# Sensor.net
KiCad netlist of a schematic drawn in Altium Designer
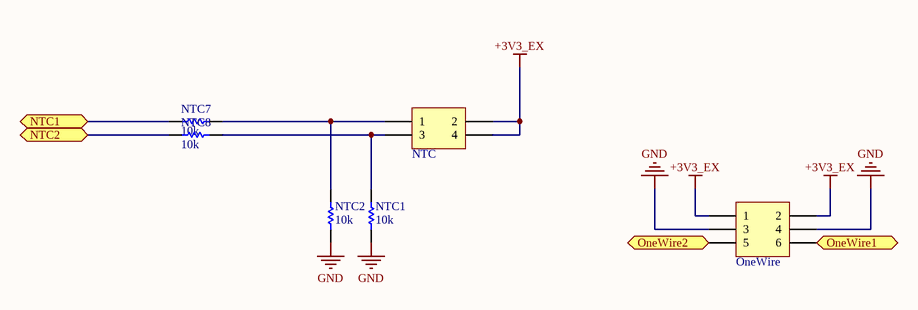
[diagram p0: Sensor.SchDoc]

(export (version "E")
  (design (tool "Eeschema 10.0.6"))
  (components
    (comp (ref "NTC")
      (value "Header 2X2")
      (footprint "heromap:HDR2X2")
      (description "Header, 2-Pin, Dual row")
      (fields (field (name "PUBLISHER") "Altium Limited"))
      (libsource (lib "heromap") (part "Header 2X2"))
    )
    (comp (ref "NTC1")
      (value "10k")
      (footprint "RESC1608N_ZERO")
      (fields (field (name "Comment") "Res"))
      (libsource (lib "Tuan") (part "Res"))
    )
    (comp (ref "NTC2")
      (value "10k")
      (footprint "RESC1608N_ZERO")
      (fields (field (name "Comment") "Res"))
      (libsource (lib "Tuan") (part "Res"))
    )
    (comp (ref "NTC7")
      (value "10k")
      (footprint "RESC1608N_ZERO")
      (fields (field (name "Comment") "Res"))
      (libsource (lib "Tuan") (part "Res"))
    )
    (comp (ref "NTC8")
      (value "10k")
      (footprint "RESC1608N_ZERO")
      (fields (field (name "Comment") "Res"))
      (libsource (lib "Tuan") (part "Res"))
    )
    (comp (ref "OneWire")
      (value "Header 3X2")
      (footprint "heromap:HDR2X3")
      (description "Header, 3-Pin, Dual row")
      (fields (field (name "PUBLISHER") "Altium Limited"))
      (libsource (lib "heromap") (part "Header 3X2"))
    )
  )
  (nets
    (net (code "1") (name "+3V3_EX") (class "Default")
      (node (ref "NTC") (pin "2") (pinfunction "2_2") (pintype "passive"))
      (node (ref "NTC") (pin "4") (pinfunction "4_4") (pintype "passive"))
      (node (ref "OneWire") (pin "1") (pinfunction "1_1") (pintype "passive"))
      (node (ref "OneWire") (pin "2") (pinfunction "2_2") (pintype "passive"))
    )
    (net (code "2") (name "/NTC1") (class "Default")
      (node (ref "NTC7") (pin "2") (pinfunction "2_2") (pintype "passive"))
    )
    (net (code "3") (name "/NTC2") (class "Default")
      (node (ref "NTC8") (pin "2") (pinfunction "2_2") (pintype "passive"))
    )
    (net (code "4") (name "/OneWire1") (class "Default")
      (node (ref "OneWire") (pin "6") (pinfunction "6_6") (pintype "passive"))
    )
    (net (code "5") (name "/OneWire2") (class "Default")
      (node (ref "OneWire") (pin "5") (pinfunction "5_5") (pintype "passive"))
    )
    (net (code "6") (name "GND") (class "Default")
      (node (ref "NTC1") (pin "1") (pinfunction "1_1") (pintype "passive"))
      (node (ref "NTC2") (pin "1") (pinfunction "1_1") (pintype "passive"))
      (node (ref "OneWire") (pin "3") (pinfunction "3_3") (pintype "passive"))
      (node (ref "OneWire") (pin "4") (pinfunction "4_4") (pintype "passive"))
    )
    (net (code "7") (name "Net-(NTC-Pad1)") (class "Default")
      (node (ref "NTC") (pin "1") (pinfunction "1_1") (pintype "passive"))
      (node (ref "NTC2") (pin "2") (pinfunction "2_2") (pintype "passive"))
      (node (ref "NTC7") (pin "1") (pinfunction "1_1") (pintype "passive"))
    )
    (net (code "8") (name "Net-(NTC-Pad3)") (class "Default")
      (node (ref "NTC") (pin "3") (pinfunction "3_3") (pintype "passive"))
      (node (ref "NTC1") (pin "2") (pinfunction "2_2") (pintype "passive"))
      (node (ref "NTC8") (pin "1") (pinfunction "1_1") (pintype "passive"))
    )
  )
)
